# usbXR.net
KiCad netlist of a schematic drawn in EAGLE
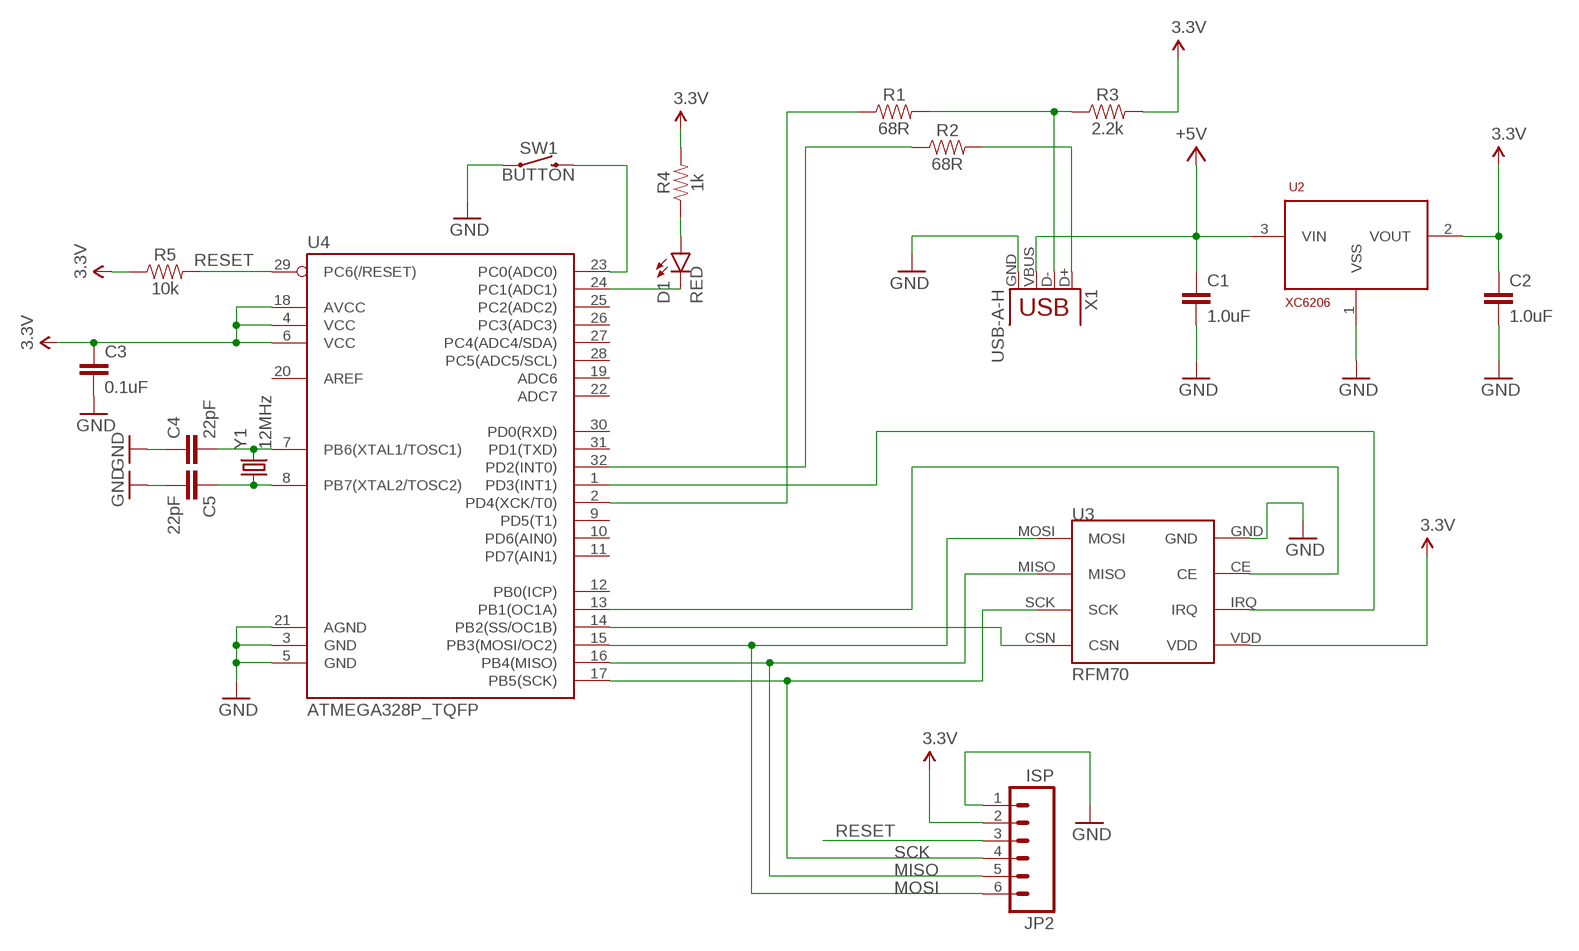
[diagram p0: schematic, sheet 1]

(export (version "E")
  (design (tool "Eeschema 10.0.6"))
  (components
    (comp (ref "C1")
      (value "1.0uF")
      (footprint "eagle-import:0603")
      (libsource (lib "eagle-import") (part "1.0UF-0603-16V-10%"))
    )
    (comp (ref "C2")
      (value "1.0uF")
      (footprint "eagle-import:0603")
      (libsource (lib "eagle-import") (part "1.0UF-0603-16V-10%"))
    )
    (comp (ref "C3")
      (value "0.1uF")
      (footprint "eagle-import:0603")
      (libsource (lib "eagle-import") (part "0.1UF-0603-25V-(+80/-20%)"))
    )
    (comp (ref "C4")
      (value "22pF")
      (footprint "eagle-import:0603")
      (libsource (lib "eagle-import") (part "22PF-0603-50V-5%"))
    )
    (comp (ref "C5")
      (value "22pF")
      (footprint "eagle-import:0603")
      (libsource (lib "eagle-import") (part "22PF-0603-50V-5%"))
    )
    (comp (ref "D1")
      (value "RED")
      (footprint "eagle-import:LED-1206")
      (libsource (lib "eagle-import") (part "LED1206"))
    )
    (comp (ref "JP2")
      (value "ISP")
      (footprint "eagle-import:1X06-SMD_EDGE")
      (libsource (lib "eagle-import") (part "M061X06-SMD_EDGE_FEMALE"))
    )
    (comp (ref "R1")
      (value "68R")
      (footprint "eagle-import:0603")
      (libsource (lib "eagle-import") (part "68OHM-0603-1/10W-1%"))
    )
    (comp (ref "R2")
      (value "68R")
      (footprint "eagle-import:0603")
      (libsource (lib "eagle-import") (part "68OHM-0603-1/10W-1%"))
    )
    (comp (ref "R3")
      (value "2.2k")
      (footprint "eagle-import:0603")
      (libsource (lib "eagle-import") (part "2.2KOHM-0603-1/10W-1%"))
    )
    (comp (ref "R4")
      (value "1k")
      (footprint "eagle-import:0603")
      (libsource (lib "eagle-import") (part "1KOHM-0603-1/10W-1%"))
    )
    (comp (ref "R5")
      (value "10k")
      (footprint "eagle-import:0603")
      (libsource (lib "eagle-import") (part "10KOHM-0603-1/10W-1%"))
    )
    (comp (ref "SW1")
      (value "BUTTON")
      (footprint "eagle-import:TACTILE_SWITCH_3X4MM")
      (libsource (lib "eagle-import") (part "TACTILE_SWITCH"))
    )
    (comp (ref "U2")
      (value "XC6206")
      (footprint "eagle-import:SOT23-3")
      (libsource (lib "eagle-import") (part "XC6206"))
    )
    (comp (ref "U3")
      (value "RFM70")
      (footprint "eagle-import:RFM70_SMD")
      (libsource (lib "eagle-import") (part "RFM70SMD_ONLY"))
    )
    (comp (ref "U4")
      (value "ATMEGA328P_TQFP")
      (footprint "eagle-import:TQFP32-08")
      (libsource (lib "eagle-import") (part "ATMEGA328P_TQFP"))
    )
    (comp (ref "X1")
      (value "USB-A-H")
      (footprint "eagle-import:USB-A-H")
      (libsource (lib "eagle-import") (part "USB-A-H"))
    )
    (comp (ref "Y1")
      (value "12MHz")
      (footprint "eagle-import:HC49US")
      (libsource (lib "eagle-import") (part "CRYSTALHC49US"))
    )
  )
  (nets
    (net (code "1") (name "+5V") (class "Default")
      (node (ref "C1") (pin "1") (pinfunction "1_1") (pintype "passive"))
      (node (ref "U2") (pin "3") (pinfunction "VIN_3") (pintype "bidirectional"))
      (node (ref "X1") (pin "VBUS") (pinfunction "VBUS_VBUS") (pintype "bidirectional"))
    )
    (net (code "2") (name "/MISO") (class "Default")
      (node (ref "JP2") (pin "5") (pinfunction "5_5") (pintype "passive"))
      (node (ref "U3") (pin "MISO") (pinfunction "MISO_MISO") (pintype "output"))
      (node (ref "U4") (pin "16") (pinfunction "PB4(MISO)_16") (pintype "bidirectional"))
    )
    (net (code "3") (name "/MOSI") (class "Default")
      (node (ref "JP2") (pin "6") (pinfunction "6_6") (pintype "passive"))
      (node (ref "U3") (pin "MOSI") (pinfunction "MOSI_MOSI") (pintype "input"))
      (node (ref "U4") (pin "15") (pinfunction "PB3(MOSI/OC2)_15") (pintype "bidirectional"))
    )
    (net (code "4") (name "/RESET") (class "Default")
      (node (ref "JP2") (pin "3") (pinfunction "3_3") (pintype "passive"))
      (node (ref "R5") (pin "2") (pinfunction "2_2") (pintype "passive"))
      (node (ref "U4") (pin "29") (pinfunction "PC6(/RESET)_29") (pintype "bidirectional"))
    )
    (net (code "5") (name "/SCK") (class "Default")
      (node (ref "JP2") (pin "4") (pinfunction "4_4") (pintype "passive"))
      (node (ref "U3") (pin "SCK") (pinfunction "SCK_SCK") (pintype "input"))
      (node (ref "U4") (pin "17") (pinfunction "PB5(SCK)_17") (pintype "bidirectional"))
    )
    (net (code "6") (name "3.3V") (class "Default")
      (node (ref "C2") (pin "1") (pinfunction "1_1") (pintype "passive"))
      (node (ref "C3") (pin "1") (pinfunction "1_1") (pintype "passive"))
      (node (ref "JP2") (pin "2") (pinfunction "2_2") (pintype "passive"))
      (node (ref "R3") (pin "2") (pinfunction "2_2") (pintype "passive"))
      (node (ref "R4") (pin "2") (pinfunction "2_2") (pintype "passive"))
      (node (ref "R5") (pin "1") (pinfunction "1_1") (pintype "passive"))
      (node (ref "U2") (pin "2") (pinfunction "VOUT_2") (pintype "bidirectional"))
      (node (ref "U3") (pin "VDD") (pinfunction "VDD_VDD") (pintype "power_in"))
      (node (ref "U4") (pin "18") (pinfunction "AVCC_18") (pintype "bidirectional"))
      (node (ref "U4") (pin "4") (pinfunction "VCC_4") (pintype "bidirectional"))
      (node (ref "U4") (pin "6") (pinfunction "VCC_6") (pintype "bidirectional"))
    )
    (net (code "7") (name "GND") (class "Default")
      (node (ref "C1") (pin "2") (pinfunction "2_2") (pintype "passive"))
      (node (ref "C2") (pin "2") (pinfunction "2_2") (pintype "passive"))
      (node (ref "C3") (pin "2") (pinfunction "2_2") (pintype "passive"))
      (node (ref "C4") (pin "1") (pinfunction "1_1") (pintype "passive"))
      (node (ref "C5") (pin "2") (pinfunction "2_2") (pintype "passive"))
      (node (ref "JP2") (pin "1") (pinfunction "1_1") (pintype "passive"))
      (node (ref "SW1") (pin "1") (pinfunction "1_1") (pintype "passive"))
      (node (ref "U2") (pin "1") (pinfunction "VSS_1") (pintype "bidirectional"))
      (node (ref "U3") (pin "GND") (pinfunction "GND_GND") (pintype "power_in"))
      (node (ref "U4") (pin "21") (pinfunction "AGND_21") (pintype "bidirectional"))
      (node (ref "U4") (pin "3") (pinfunction "GND_3") (pintype "bidirectional"))
      (node (ref "U4") (pin "5") (pinfunction "GND_5") (pintype "bidirectional"))
      (node (ref "X1") (pin "GND") (pinfunction "GND_GND") (pintype "bidirectional"))
    )
    (net (code "8") (name "Net-(D1-PadA)") (class "Default")
      (node (ref "D1") (pin "A") (pinfunction "A_A") (pintype "passive"))
      (node (ref "R4") (pin "1") (pinfunction "1_1") (pintype "passive"))
    )
    (net (code "9") (name "Net-(R1-Pad2)") (class "Default")
      (node (ref "R1") (pin "2") (pinfunction "2_2") (pintype "passive"))
      (node (ref "R3") (pin "1") (pinfunction "1_1") (pintype "passive"))
      (node (ref "X1") (pin "D-") (pinfunction "D-_D-") (pintype "bidirectional"))
    )
    (net (code "10") (name "Net-(R2-Pad2)") (class "Default")
      (node (ref "R2") (pin "2") (pinfunction "2_2") (pintype "passive"))
      (node (ref "X1") (pin "D+") (pinfunction "D+_D+") (pintype "bidirectional"))
    )
    (net (code "11") (name "Net-(U4-PB1(OC1A))") (class "Default")
      (node (ref "U3") (pin "CE") (pinfunction "CE_CE") (pintype "input"))
      (node (ref "U4") (pin "13") (pinfunction "PB1(OC1A)_13") (pintype "bidirectional"))
    )
    (net (code "12") (name "Net-(U4-PB2(SS{slash}OC1B))") (class "Default")
      (node (ref "U3") (pin "CSN") (pinfunction "CSN_CSN") (pintype "input"))
      (node (ref "U4") (pin "14") (pinfunction "PB2(SS/OC1B)_14") (pintype "bidirectional"))
    )
    (net (code "13") (name "Net-(U4-PB6(XTAL1{slash}TOSC1))") (class "Default")
      (node (ref "C4") (pin "2") (pinfunction "2_2") (pintype "passive"))
      (node (ref "U4") (pin "7") (pinfunction "PB6(XTAL1/TOSC1)_7") (pintype "bidirectional"))
      (node (ref "Y1") (pin "2") (pinfunction "2_2") (pintype "passive"))
    )
    (net (code "14") (name "Net-(U4-PB7(XTAL2{slash}TOSC2))") (class "Default")
      (node (ref "C5") (pin "1") (pinfunction "1_1") (pintype "passive"))
      (node (ref "U4") (pin "8") (pinfunction "PB7(XTAL2/TOSC2)_8") (pintype "bidirectional"))
      (node (ref "Y1") (pin "1") (pinfunction "1_1") (pintype "passive"))
    )
    (net (code "15") (name "Net-(U4-PC0(ADC0))") (class "Default")
      (node (ref "SW1") (pin "2") (pinfunction "2_2") (pintype "passive"))
      (node (ref "U4") (pin "23") (pinfunction "PC0(ADC0)_23") (pintype "bidirectional"))
    )
    (net (code "16") (name "Net-(U4-PC1(ADC1))") (class "Default")
      (node (ref "D1") (pin "C") (pinfunction "C_C") (pintype "passive"))
      (node (ref "U4") (pin "24") (pinfunction "PC1(ADC1)_24") (pintype "bidirectional"))
    )
    (net (code "17") (name "Net-(U4-PD2(INT0))") (class "Default")
      (node (ref "R2") (pin "1") (pinfunction "1_1") (pintype "passive"))
      (node (ref "U4") (pin "32") (pinfunction "PD2(INT0)_32") (pintype "bidirectional"))
    )
    (net (code "18") (name "Net-(U4-PD3(INT1))") (class "Default")
      (node (ref "U3") (pin "IRQ") (pinfunction "IRQ_IRQ") (pintype "output"))
      (node (ref "U4") (pin "1") (pinfunction "PD3(INT1)_1") (pintype "bidirectional"))
    )
    (net (code "19") (name "Net-(U4-PD4(XCK{slash}T0))") (class "Default")
      (node (ref "R1") (pin "1") (pinfunction "1_1") (pintype "passive"))
      (node (ref "U4") (pin "2") (pinfunction "PD4(XCK/T0)_2") (pintype "bidirectional"))
    )
    (net (code "20") (name "unconnected-(U4-ADC6-Pad19)") (class "Default")
      (node (ref "U4") (pin "19") (pinfunction "ADC6_19") (pintype "bidirectional"))
    )
    (net (code "21") (name "unconnected-(U4-ADC7-Pad22)") (class "Default")
      (node (ref "U4") (pin "22") (pinfunction "ADC7_22") (pintype "bidirectional"))
    )
    (net (code "22") (name "unconnected-(U4-AREF-Pad20)") (class "Default")
      (node (ref "U4") (pin "20") (pinfunction "AREF_20") (pintype "bidirectional"))
    )
    (net (code "23") (name "unconnected-(U4-PB0(ICP)-Pad12)") (class "Default")
      (node (ref "U4") (pin "12") (pinfunction "PB0(ICP)_12") (pintype "bidirectional"))
    )
    (net (code "24") (name "unconnected-(U4-PC2(ADC2)-Pad25)") (class "Default")
      (node (ref "U4") (pin "25") (pinfunction "PC2(ADC2)_25") (pintype "bidirectional"))
    )
    (net (code "25") (name "unconnected-(U4-PC3(ADC3)-Pad26)") (class "Default")
      (node (ref "U4") (pin "26") (pinfunction "PC3(ADC3)_26") (pintype "bidirectional"))
    )
    (net (code "26") (name "unconnected-(U4-PC4(ADC4{slash}SDA)-Pad27)") (class "Default")
      (node (ref "U4") (pin "27") (pinfunction "PC4(ADC4/SDA)_27") (pintype "bidirectional"))
    )
    (net (code "27") (name "unconnected-(U4-PC5(ADC5{slash}SCL)-Pad28)") (class "Default")
      (node (ref "U4") (pin "28") (pinfunction "PC5(ADC5/SCL)_28") (pintype "bidirectional"))
    )
    (net (code "28") (name "unconnected-(U4-PD0(RXD)-Pad30)") (class "Default")
      (node (ref "U4") (pin "30") (pinfunction "PD0(RXD)_30") (pintype "bidirectional"))
    )
    (net (code "29") (name "unconnected-(U4-PD1(TXD)-Pad31)") (class "Default")
      (node (ref "U4") (pin "31") (pinfunction "PD1(TXD)_31") (pintype "bidirectional"))
    )
    (net (code "30") (name "unconnected-(U4-PD5(T1)-Pad9)") (class "Default")
      (node (ref "U4") (pin "9") (pinfunction "PD5(T1)_9") (pintype "bidirectional"))
    )
    (net (code "31") (name "unconnected-(U4-PD6(AIN0)-Pad10)") (class "Default")
      (node (ref "U4") (pin "10") (pinfunction "PD6(AIN0)_10") (pintype "bidirectional"))
    )
    (net (code "32") (name "unconnected-(U4-PD7(AIN1)-Pad11)") (class "Default")
      (node (ref "U4") (pin "11") (pinfunction "PD7(AIN1)_11") (pintype "bidirectional"))
    )
  )
)
